# SolderDispenser_v1_1.net
KiCad netlist of a schematic drawn in EAGLE
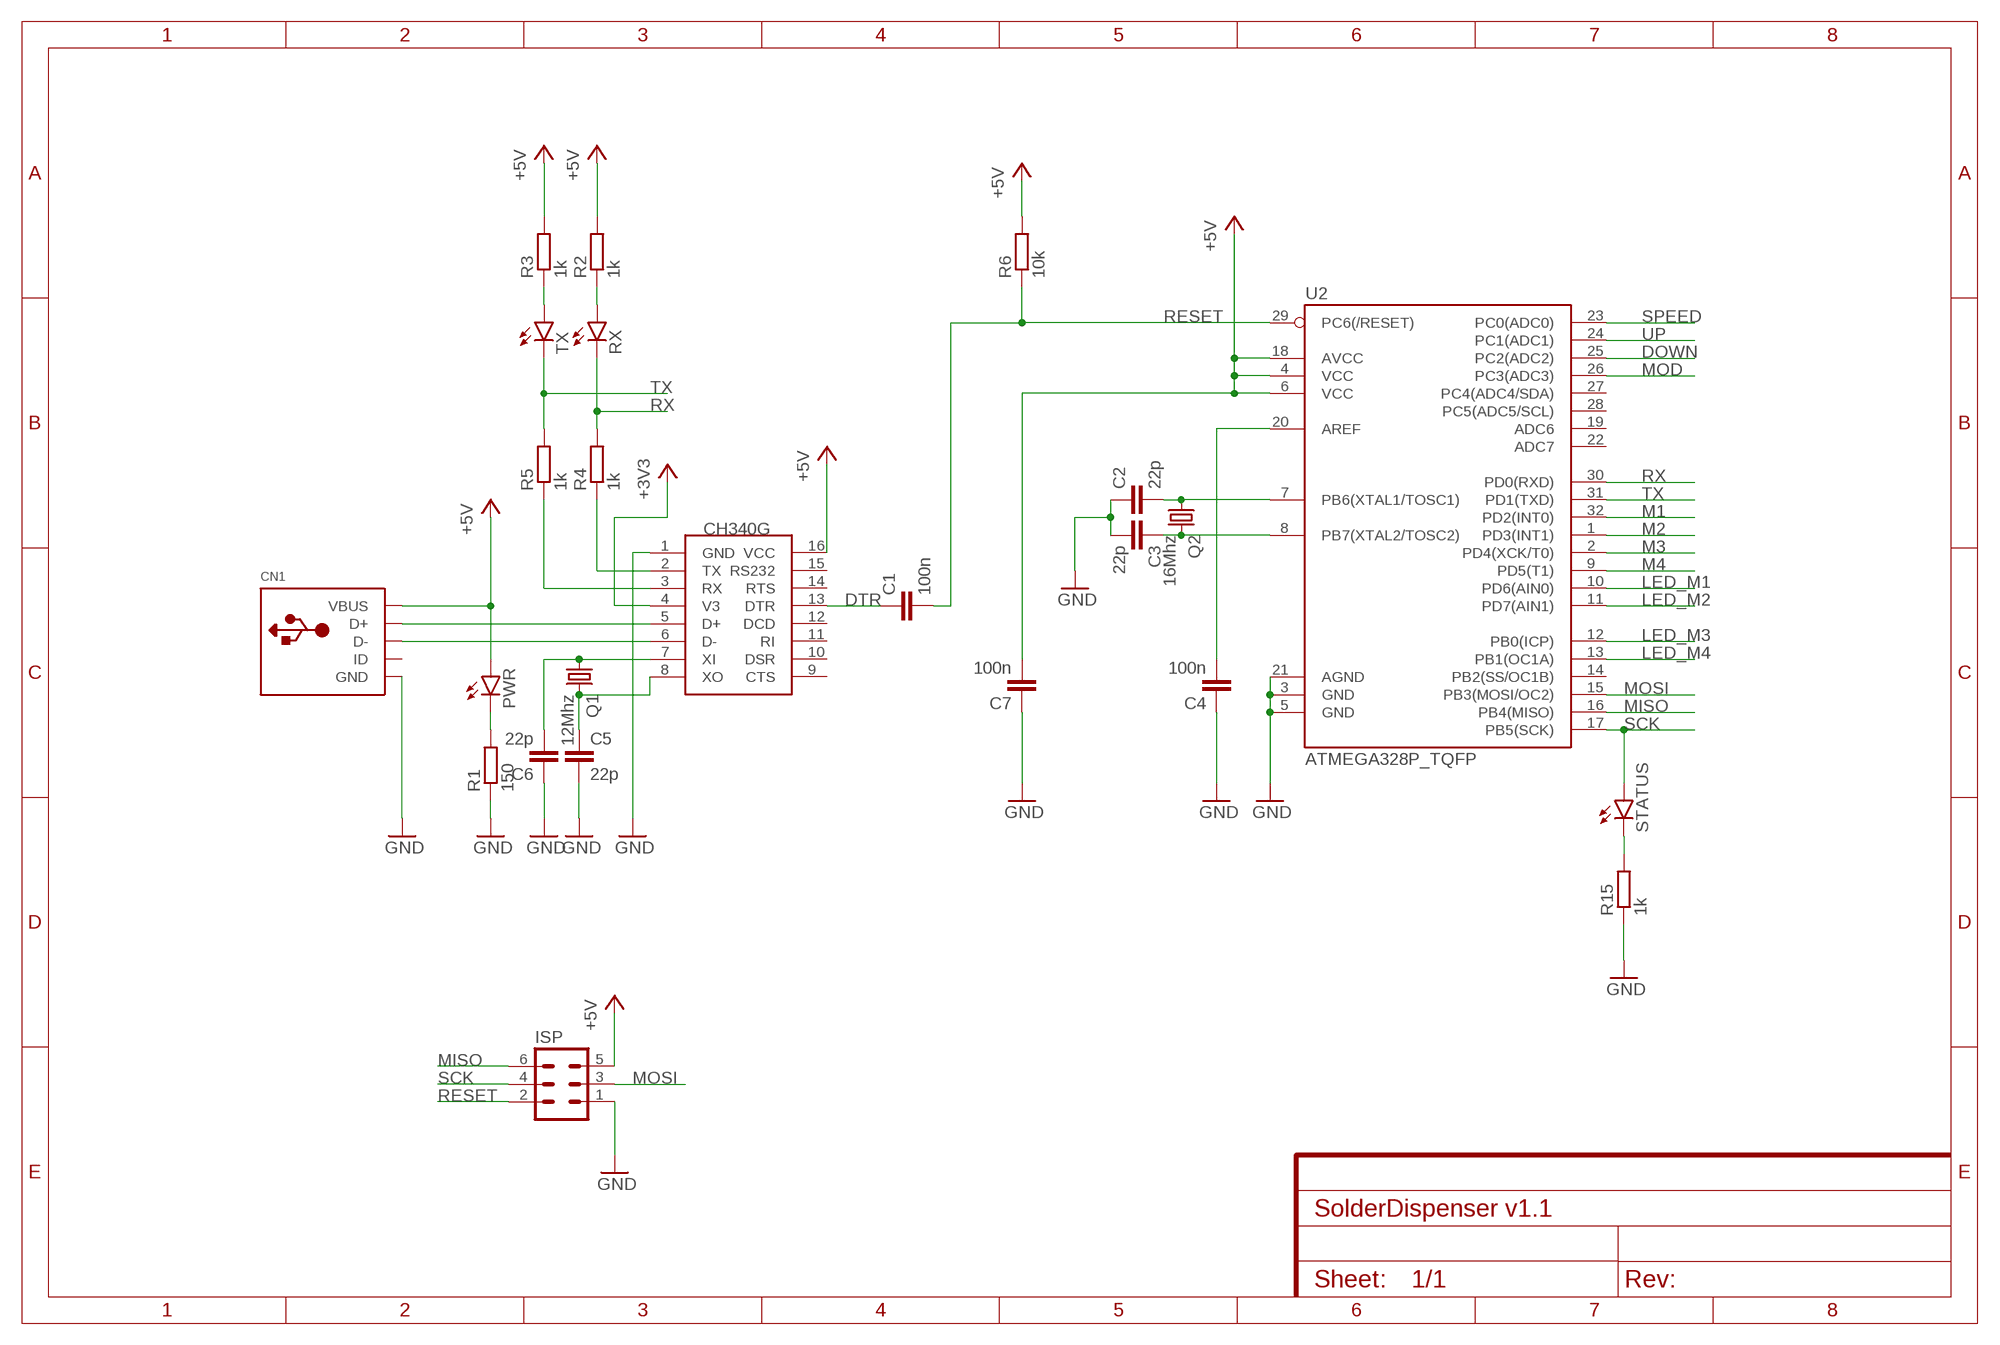
[diagram p0: schematic, sheet 1, part 1 of 2]
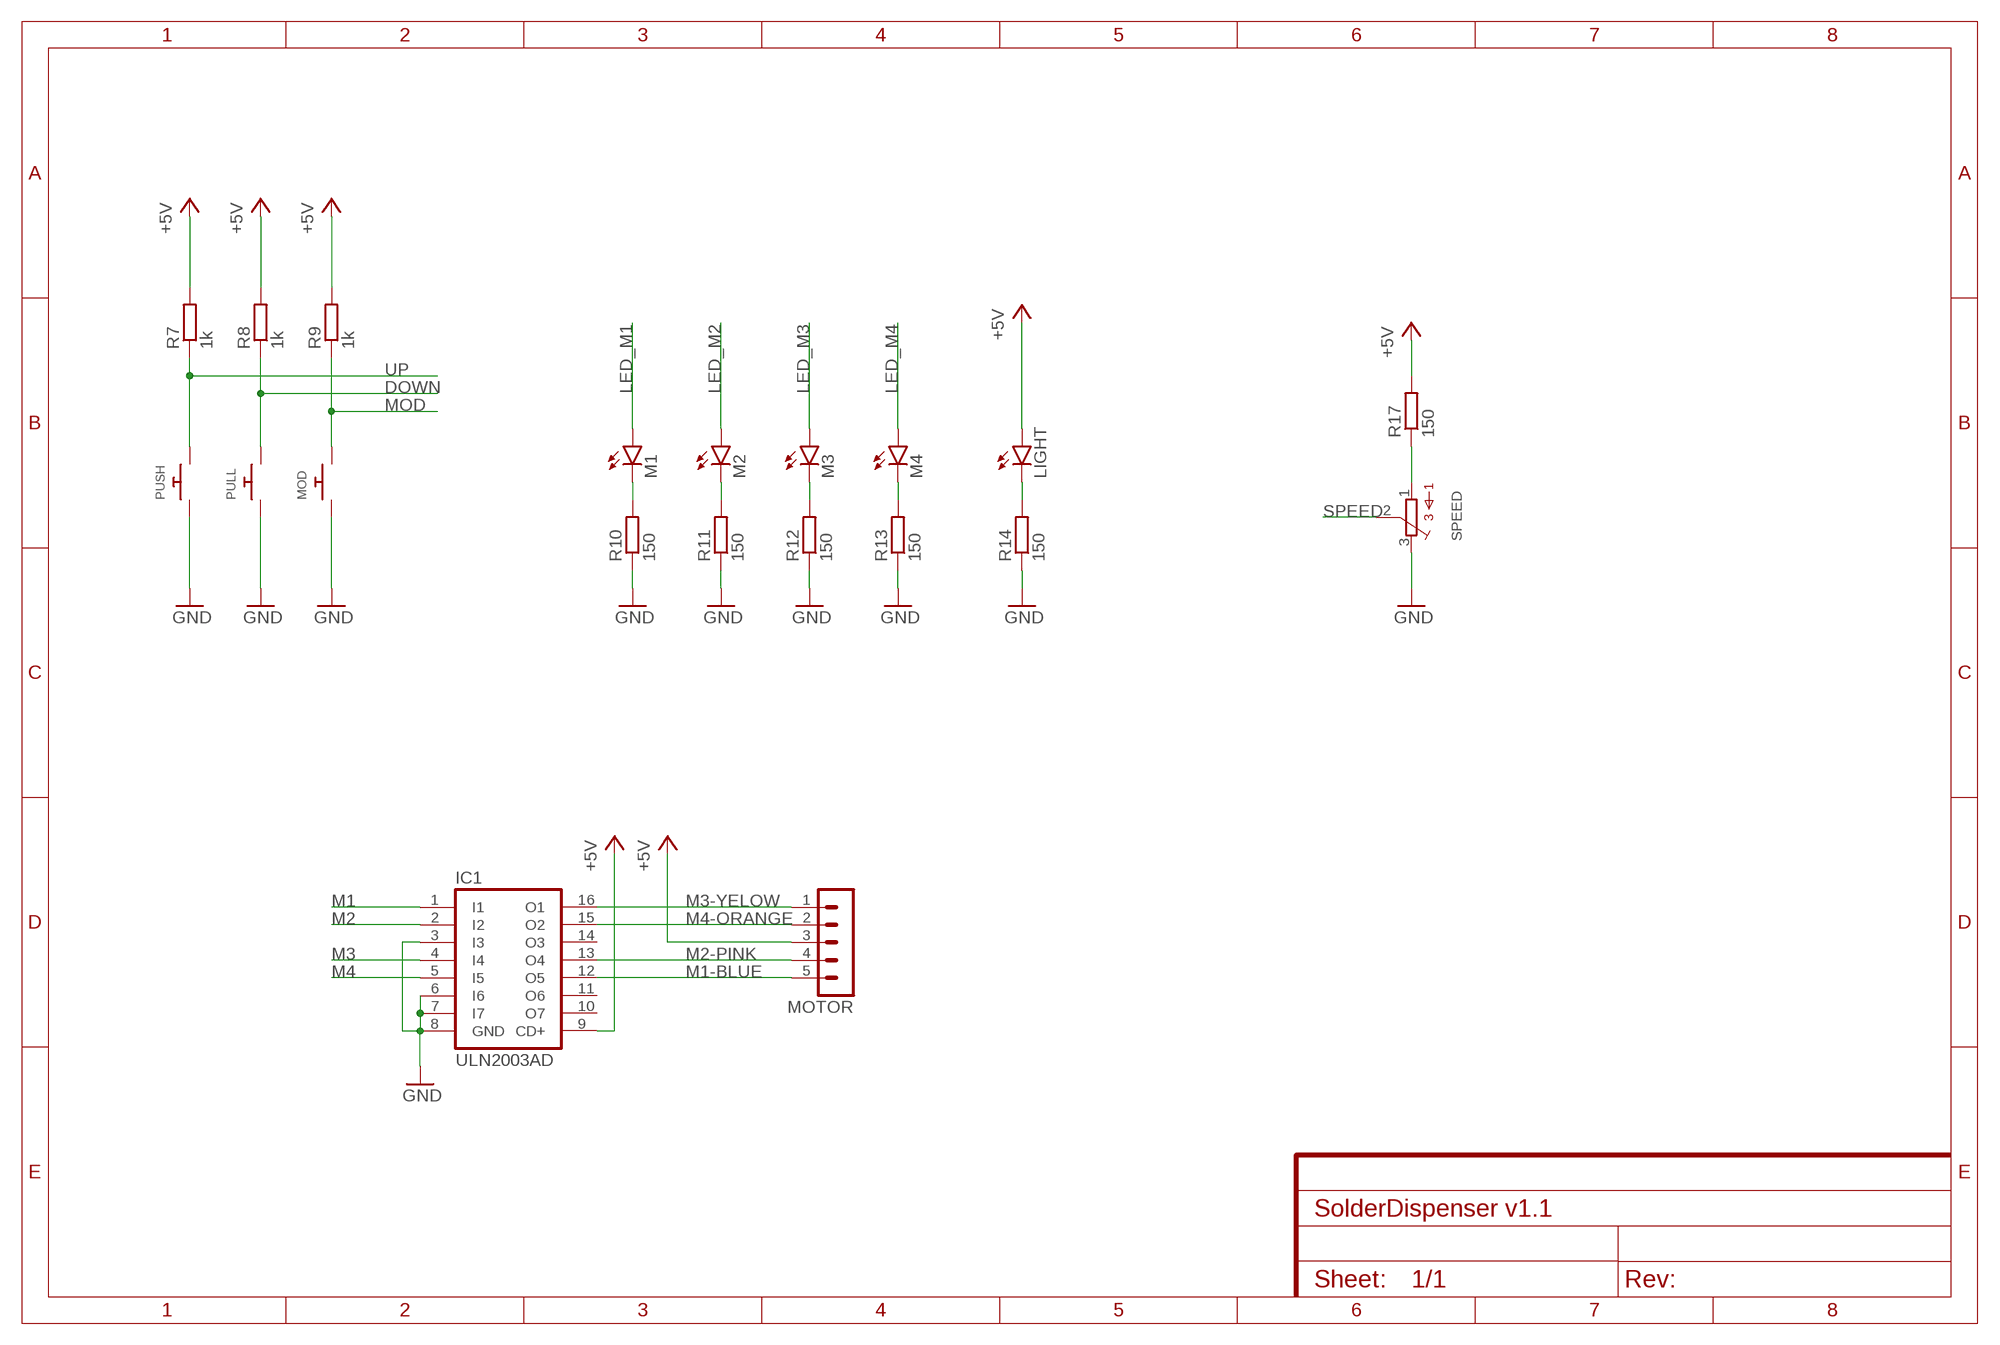
[diagram p1: schematic, sheet 1, part 2 of 2]

(export (version "E")
  (design (tool "Eeschema 10.0.6"))
  (components
    (comp (ref "C1")
      (value "100n")
      (footprint "eagle-import:C0805")
      (libsource (lib "eagle-import") (part "C-EUC0805"))
    )
    (comp (ref "C2")
      (value "22p")
      (footprint "eagle-import:C0805")
      (libsource (lib "eagle-import") (part "C-EUC0805"))
    )
    (comp (ref "C3")
      (value "22p")
      (footprint "eagle-import:C0805")
      (libsource (lib "eagle-import") (part "C-EUC0805"))
    )
    (comp (ref "C4")
      (value "100n")
      (footprint "eagle-import:C0805")
      (libsource (lib "eagle-import") (part "C-EUC0805"))
    )
    (comp (ref "C5")
      (value "22p")
      (footprint "eagle-import:C0805")
      (libsource (lib "eagle-import") (part "C-EUC0805"))
    )
    (comp (ref "C6")
      (value "22p")
      (footprint "eagle-import:C0805")
      (libsource (lib "eagle-import") (part "C-EUC0805"))
    )
    (comp (ref "C7")
      (value "100n")
      (footprint "eagle-import:C0805")
      (libsource (lib "eagle-import") (part "C-EUC0805"))
    )
    (comp (ref "CN1")
      (value "USBMOLEX")
      (footprint "eagle-import:USB-MINIB-THM-MOLEX")
      (libsource (lib "eagle-import") (part "USBMOLEX"))
    )
    (comp (ref "IC1")
      (value "ULN2003AD")
      (footprint "eagle-import:SO16")
      (libsource (lib "eagle-import") (part "ULN2003AD"))
    )
    (comp (ref "ISP")
      (value "MA03-2")
      (footprint "eagle-import:MA03-2")
      (libsource (lib "eagle-import") (part "MA03-2"))
    )
    (comp (ref "LIGHT")
      (value "LED5MM")
      (footprint "eagle-import:LED5MM")
      (libsource (lib "eagle-import") (part "LED5MM"))
    )
    (comp (ref "M1")
      (value "LEDSML0805")
      (footprint "eagle-import:SML0805")
      (libsource (lib "eagle-import") (part "LEDSML0805"))
    )
    (comp (ref "M2")
      (value "LEDSML0805")
      (footprint "eagle-import:SML0805")
      (libsource (lib "eagle-import") (part "LEDSML0805"))
    )
    (comp (ref "M3")
      (value "LEDSML0805")
      (footprint "eagle-import:SML0805")
      (libsource (lib "eagle-import") (part "LEDSML0805"))
    )
    (comp (ref "M4")
      (value "LEDSML0805")
      (footprint "eagle-import:SML0805")
      (libsource (lib "eagle-import") (part "LEDSML0805"))
    )
    (comp (ref "MOD")
      (value "SWITCH_PUSHBUTTONEVQ-PE")
      (footprint "eagle-import:TACT_PANA-EVQ")
      (libsource (lib "eagle-import") (part "SWITCH_PUSHBUTTONEVQ-PE"))
    )
    (comp (ref "MOTOR")
      (value "MA05-1")
      (footprint "eagle-import:MA05-1")
      (libsource (lib "eagle-import") (part "MA05-1"))
    )
    (comp (ref "PULL")
      (value "SWITCH_PUSHBUTTONEVQ-PE")
      (footprint "eagle-import:TACT_PANA-EVQ")
      (libsource (lib "eagle-import") (part "SWITCH_PUSHBUTTONEVQ-PE"))
    )
    (comp (ref "PUSH")
      (value "SWITCH_PUSHBUTTONEVQ-PE")
      (footprint "eagle-import:TACT_PANA-EVQ")
      (libsource (lib "eagle-import") (part "SWITCH_PUSHBUTTONEVQ-PE"))
    )
    (comp (ref "PWR")
      (value "LEDSML0805")
      (footprint "eagle-import:SML0805")
      (libsource (lib "eagle-import") (part "LEDSML0805"))
    )
    (comp (ref "Q1")
      (value "12Mhz")
      (footprint "eagle-import:HC49UP")
      (libsource (lib "eagle-import") (part "CRYSTALHC49UP"))
    )
    (comp (ref "Q2")
      (value "16Mhz")
      (footprint "eagle-import:HC49UP")
      (libsource (lib "eagle-import") (part "CRYSTALHC49UP"))
    )
    (comp (ref "R1")
      (value "150")
      (footprint "eagle-import:R0805")
      (libsource (lib "eagle-import") (part "R-EU_R0805"))
    )
    (comp (ref "R2")
      (value "1k")
      (footprint "eagle-import:R0805")
      (libsource (lib "eagle-import") (part "R-EU_R0805"))
    )
    (comp (ref "R3")
      (value "1k")
      (footprint "eagle-import:R0805")
      (libsource (lib "eagle-import") (part "R-EU_R0805"))
    )
    (comp (ref "R4")
      (value "1k")
      (footprint "eagle-import:R0805")
      (libsource (lib "eagle-import") (part "R-EU_R0805"))
    )
    (comp (ref "R5")
      (value "1k")
      (footprint "eagle-import:R0805")
      (libsource (lib "eagle-import") (part "R-EU_R0805"))
    )
    (comp (ref "R6")
      (value "10k")
      (footprint "eagle-import:R0805")
      (libsource (lib "eagle-import") (part "R-EU_R0805"))
    )
    (comp (ref "R7")
      (value "1k")
      (footprint "eagle-import:R0805")
      (libsource (lib "eagle-import") (part "R-EU_R0805"))
    )
    (comp (ref "R8")
      (value "1k")
      (footprint "eagle-import:R0805")
      (libsource (lib "eagle-import") (part "R-EU_R0805"))
    )
    (comp (ref "R9")
      (value "1k")
      (footprint "eagle-import:R0805")
      (libsource (lib "eagle-import") (part "R-EU_R0805"))
    )
    (comp (ref "R10")
      (value "150")
      (footprint "eagle-import:R0805")
      (libsource (lib "eagle-import") (part "R-EU_R0805"))
    )
    (comp (ref "R11")
      (value "150")
      (footprint "eagle-import:R0805")
      (libsource (lib "eagle-import") (part "R-EU_R0805"))
    )
    (comp (ref "R12")
      (value "150")
      (footprint "eagle-import:R0805")
      (libsource (lib "eagle-import") (part "R-EU_R0805"))
    )
    (comp (ref "R13")
      (value "150")
      (footprint "eagle-import:R0805")
      (libsource (lib "eagle-import") (part "R-EU_R0805"))
    )
    (comp (ref "R14")
      (value "150")
      (footprint "eagle-import:R0805")
      (libsource (lib "eagle-import") (part "R-EU_R0805"))
    )
    (comp (ref "R15")
      (value "1k")
      (footprint "eagle-import:R0805")
      (libsource (lib "eagle-import") (part "R-EU_R0805"))
    )
    (comp (ref "R17")
      (value "150")
      (footprint "eagle-import:R0805")
      (libsource (lib "eagle-import") (part "R-EU_R0805"))
    )
    (comp (ref "RX")
      (value "LEDSML0805")
      (footprint "eagle-import:SML0805")
      (libsource (lib "eagle-import") (part "LEDSML0805"))
    )
    (comp (ref "SPEED")
      (value "3362P")
      (footprint "eagle-import:3362P")
      (libsource (lib "eagle-import") (part "3362P"))
    )
    (comp (ref "STATUS")
      (value "LEDSML0805")
      (footprint "eagle-import:SML0805")
      (libsource (lib "eagle-import") (part "LEDSML0805"))
    )
    (comp (ref "TX")
      (value "LEDSML0805")
      (footprint "eagle-import:SML0805")
      (libsource (lib "eagle-import") (part "LEDSML0805"))
    )
    (comp (ref "U$1")
      (value "CH340G")
      (footprint "eagle-import:SOIC16")
      (libsource (lib "eagle-import") (part "CH340G"))
    )
    (comp (ref "U2")
      (value "ATMEGA328P_TQFP")
      (footprint "eagle-import:TQFP32-08")
      (libsource (lib "eagle-import") (part "ATMEGA328P_TQFP"))
    )
  )
  (nets
    (net (code "1") (name "+3V3") (class "Default")
      (node (ref "U$1") (pin "4") (pinfunction "V3_4") (pintype "bidirectional"))
    )
    (net (code "2") (name "+5V") (class "Default")
      (node (ref "C7") (pin "2") (pinfunction "2_2") (pintype "passive"))
      (node (ref "CN1") (pin "VBUS") (pinfunction "VBUS_VBUS") (pintype "power_in"))
      (node (ref "IC1") (pin "9") (pinfunction "CD+_9") (pintype "passive"))
      (node (ref "ISP") (pin "5") (pinfunction "5_5") (pintype "passive"))
      (node (ref "LIGHT") (pin "A") (pinfunction "A_A") (pintype "passive"))
      (node (ref "MOTOR") (pin "3") (pinfunction "3_3") (pintype "passive"))
      (node (ref "PWR") (pin "A") (pinfunction "A_A") (pintype "passive"))
      (node (ref "R17") (pin "2") (pinfunction "2_2") (pintype "passive"))
      (node (ref "R2") (pin "2") (pinfunction "2_2") (pintype "passive"))
      (node (ref "R3") (pin "2") (pinfunction "2_2") (pintype "passive"))
      (node (ref "R6") (pin "2") (pinfunction "2_2") (pintype "passive"))
      (node (ref "R7") (pin "2") (pinfunction "2_2") (pintype "passive"))
      (node (ref "R8") (pin "2") (pinfunction "2_2") (pintype "passive"))
      (node (ref "R9") (pin "2") (pinfunction "2_2") (pintype "passive"))
      (node (ref "U$1") (pin "16") (pinfunction "VCC_16") (pintype "bidirectional"))
      (node (ref "U2") (pin "18") (pinfunction "AVCC_18") (pintype "bidirectional"))
      (node (ref "U2") (pin "4") (pinfunction "VCC_4") (pintype "bidirectional"))
      (node (ref "U2") (pin "6") (pinfunction "VCC_6") (pintype "bidirectional"))
    )
    (net (code "3") (name "/DOWN") (class "Default")
      (node (ref "PULL") (pin "P$2") (pinfunction "P$2_P$2") (pintype "passive"))
      (node (ref "R8") (pin "1") (pinfunction "1_1") (pintype "passive"))
      (node (ref "U2") (pin "25") (pinfunction "PC2(ADC2)_25") (pintype "bidirectional"))
    )
    (net (code "4") (name "/DTR") (class "Default")
      (node (ref "C1") (pin "1") (pinfunction "1_1") (pintype "passive"))
      (node (ref "U$1") (pin "13") (pinfunction "DTR_13") (pintype "bidirectional"))
    )
    (net (code "5") (name "/LED_M1") (class "Default")
      (node (ref "M1") (pin "A") (pinfunction "A_A") (pintype "passive"))
      (node (ref "U2") (pin "10") (pinfunction "PD6(AIN0)_10") (pintype "bidirectional"))
    )
    (net (code "6") (name "/LED_M2") (class "Default")
      (node (ref "M2") (pin "A") (pinfunction "A_A") (pintype "passive"))
      (node (ref "U2") (pin "11") (pinfunction "PD7(AIN1)_11") (pintype "bidirectional"))
    )
    (net (code "7") (name "/LED_M3") (class "Default")
      (node (ref "M3") (pin "A") (pinfunction "A_A") (pintype "passive"))
      (node (ref "U2") (pin "12") (pinfunction "PB0(ICP)_12") (pintype "bidirectional"))
    )
    (net (code "8") (name "/LED_M4") (class "Default")
      (node (ref "M4") (pin "A") (pinfunction "A_A") (pintype "passive"))
      (node (ref "U2") (pin "13") (pinfunction "PB1(OC1A)_13") (pintype "bidirectional"))
    )
    (net (code "9") (name "/M1") (class "Default")
      (node (ref "IC1") (pin "1") (pinfunction "I1_1") (pintype "input"))
      (node (ref "U2") (pin "32") (pinfunction "PD2(INT0)_32") (pintype "bidirectional"))
    )
    (net (code "10") (name "/M1-BLUE") (class "Default")
      (node (ref "IC1") (pin "12") (pinfunction "O5_12") (pintype "open_collector"))
      (node (ref "MOTOR") (pin "5") (pinfunction "5_5") (pintype "passive"))
    )
    (net (code "11") (name "/M2") (class "Default")
      (node (ref "IC1") (pin "2") (pinfunction "I2_2") (pintype "input"))
      (node (ref "U2") (pin "1") (pinfunction "PD3(INT1)_1") (pintype "bidirectional"))
    )
    (net (code "12") (name "/M2-PINK") (class "Default")
      (node (ref "IC1") (pin "13") (pinfunction "O4_13") (pintype "open_collector"))
      (node (ref "MOTOR") (pin "4") (pinfunction "4_4") (pintype "passive"))
    )
    (net (code "13") (name "/M3") (class "Default")
      (node (ref "IC1") (pin "4") (pinfunction "I4_4") (pintype "input"))
      (node (ref "U2") (pin "2") (pinfunction "PD4(XCK/T0)_2") (pintype "bidirectional"))
    )
    (net (code "14") (name "/M3-YELOW") (class "Default")
      (node (ref "IC1") (pin "16") (pinfunction "O1_16") (pintype "open_collector"))
      (node (ref "MOTOR") (pin "1") (pinfunction "1_1") (pintype "passive"))
    )
    (net (code "15") (name "/M4") (class "Default")
      (node (ref "IC1") (pin "5") (pinfunction "I5_5") (pintype "input"))
      (node (ref "U2") (pin "9") (pinfunction "PD5(T1)_9") (pintype "bidirectional"))
    )
    (net (code "16") (name "/M4-ORANGE") (class "Default")
      (node (ref "IC1") (pin "15") (pinfunction "O2_15") (pintype "open_collector"))
      (node (ref "MOTOR") (pin "2") (pinfunction "2_2") (pintype "passive"))
    )
    (net (code "17") (name "/MISO") (class "Default")
      (node (ref "ISP") (pin "6") (pinfunction "6_6") (pintype "passive"))
      (node (ref "U2") (pin "16") (pinfunction "PB4(MISO)_16") (pintype "bidirectional"))
    )
    (net (code "18") (name "/MOD") (class "Default")
      (node (ref "MOD") (pin "P$2") (pinfunction "P$2_P$2") (pintype "passive"))
      (node (ref "R9") (pin "1") (pinfunction "1_1") (pintype "passive"))
      (node (ref "U2") (pin "26") (pinfunction "PC3(ADC3)_26") (pintype "bidirectional"))
    )
    (net (code "19") (name "/MOSI") (class "Default")
      (node (ref "ISP") (pin "3") (pinfunction "3_3") (pintype "passive"))
      (node (ref "U2") (pin "15") (pinfunction "PB3(MOSI/OC2)_15") (pintype "bidirectional"))
    )
    (net (code "20") (name "/RESET") (class "Default")
      (node (ref "C1") (pin "2") (pinfunction "2_2") (pintype "passive"))
      (node (ref "ISP") (pin "2") (pinfunction "2_2") (pintype "passive"))
      (node (ref "R6") (pin "1") (pinfunction "1_1") (pintype "passive"))
      (node (ref "U2") (pin "29") (pinfunction "PC6(/RESET)_29") (pintype "bidirectional"))
    )
    (net (code "21") (name "/RX") (class "Default")
      (node (ref "R4") (pin "2") (pinfunction "2_2") (pintype "passive"))
      (node (ref "RX") (pin "C") (pinfunction "C_C") (pintype "passive"))
      (node (ref "U2") (pin "30") (pinfunction "PD0(RXD)_30") (pintype "bidirectional"))
    )
    (net (code "22") (name "/SCK") (class "Default")
      (node (ref "ISP") (pin "4") (pinfunction "4_4") (pintype "passive"))
      (node (ref "STATUS") (pin "A") (pinfunction "A_A") (pintype "passive"))
      (node (ref "U2") (pin "17") (pinfunction "PB5(SCK)_17") (pintype "bidirectional"))
    )
    (net (code "23") (name "/SPEED") (class "Default")
      (node (ref "SPEED") (pin "2") (pinfunction "2_2") (pintype "passive"))
      (node (ref "U2") (pin "23") (pinfunction "PC0(ADC0)_23") (pintype "bidirectional"))
    )
    (net (code "24") (name "/TX") (class "Default")
      (node (ref "R5") (pin "2") (pinfunction "2_2") (pintype "passive"))
      (node (ref "TX") (pin "C") (pinfunction "C_C") (pintype "passive"))
      (node (ref "U2") (pin "31") (pinfunction "PD1(TXD)_31") (pintype "bidirectional"))
    )
    (net (code "25") (name "/UP") (class "Default")
      (node (ref "PUSH") (pin "P$2") (pinfunction "P$2_P$2") (pintype "passive"))
      (node (ref "R7") (pin "1") (pinfunction "1_1") (pintype "passive"))
      (node (ref "U2") (pin "24") (pinfunction "PC1(ADC1)_24") (pintype "bidirectional"))
    )
    (net (code "26") (name "GND") (class "Default")
      (node (ref "C2") (pin "1") (pinfunction "1_1") (pintype "passive"))
      (node (ref "C3") (pin "2") (pinfunction "2_2") (pintype "passive"))
      (node (ref "C4") (pin "1") (pinfunction "1_1") (pintype "passive"))
      (node (ref "C5") (pin "2") (pinfunction "2_2") (pintype "passive"))
      (node (ref "C6") (pin "1") (pinfunction "1_1") (pintype "passive"))
      (node (ref "C7") (pin "1") (pinfunction "1_1") (pintype "passive"))
      (node (ref "CN1") (pin "GND") (pinfunction "GND_GND") (pintype "power_in"))
      (node (ref "IC1") (pin "3") (pinfunction "I3_3") (pintype "input"))
      (node (ref "IC1") (pin "6") (pinfunction "I6_6") (pintype "input"))
      (node (ref "IC1") (pin "7") (pinfunction "I7_7") (pintype "input"))
      (node (ref "IC1") (pin "8") (pinfunction "GND_8") (pintype "power_in"))
      (node (ref "ISP") (pin "1") (pinfunction "1_1") (pintype "passive"))
      (node (ref "MOD") (pin "P$1") (pinfunction "P$1_P$1") (pintype "passive"))
      (node (ref "PULL") (pin "P$1") (pinfunction "P$1_P$1") (pintype "passive"))
      (node (ref "PUSH") (pin "P$1") (pinfunction "P$1_P$1") (pintype "passive"))
      (node (ref "R1") (pin "1") (pinfunction "1_1") (pintype "passive"))
      (node (ref "R10") (pin "1") (pinfunction "1_1") (pintype "passive"))
      (node (ref "R11") (pin "1") (pinfunction "1_1") (pintype "passive"))
      (node (ref "R12") (pin "1") (pinfunction "1_1") (pintype "passive"))
      (node (ref "R13") (pin "1") (pinfunction "1_1") (pintype "passive"))
      (node (ref "R14") (pin "1") (pinfunction "1_1") (pintype "passive"))
      (node (ref "R15") (pin "1") (pinfunction "1_1") (pintype "passive"))
      (node (ref "SPEED") (pin "3") (pinfunction "3_3") (pintype "passive"))
      (node (ref "U$1") (pin "1") (pinfunction "GND_1") (pintype "bidirectional"))
      (node (ref "U2") (pin "21") (pinfunction "AGND_21") (pintype "bidirectional"))
      (node (ref "U2") (pin "3") (pinfunction "GND_3") (pintype "bidirectional"))
      (node (ref "U2") (pin "5") (pinfunction "GND_5") (pintype "bidirectional"))
    )
    (net (code "27") (name "Net-(LIGHT-C)") (class "Default")
      (node (ref "LIGHT") (pin "K") (pinfunction "C_K") (pintype "passive"))
      (node (ref "R14") (pin "2") (pinfunction "2_2") (pintype "passive"))
    )
    (net (code "28") (name "Net-(M1-PadC)") (class "Default")
      (node (ref "M1") (pin "C") (pinfunction "C_C") (pintype "passive"))
      (node (ref "R10") (pin "2") (pinfunction "2_2") (pintype "passive"))
    )
    (net (code "29") (name "Net-(M2-PadC)") (class "Default")
      (node (ref "M2") (pin "C") (pinfunction "C_C") (pintype "passive"))
      (node (ref "R11") (pin "2") (pinfunction "2_2") (pintype "passive"))
    )
    (net (code "30") (name "Net-(M3-PadC)") (class "Default")
      (node (ref "M3") (pin "C") (pinfunction "C_C") (pintype "passive"))
      (node (ref "R12") (pin "2") (pinfunction "2_2") (pintype "passive"))
    )
    (net (code "31") (name "Net-(M4-PadC)") (class "Default")
      (node (ref "M4") (pin "C") (pinfunction "C_C") (pintype "passive"))
      (node (ref "R13") (pin "2") (pinfunction "2_2") (pintype "passive"))
    )
    (net (code "32") (name "Net-(PWR-PadC)") (class "Default")
      (node (ref "PWR") (pin "C") (pinfunction "C_C") (pintype "passive"))
      (node (ref "R1") (pin "2") (pinfunction "2_2") (pintype "passive"))
    )
    (net (code "33") (name "Net-(R2-Pad1)") (class "Default")
      (node (ref "R2") (pin "1") (pinfunction "1_1") (pintype "passive"))
      (node (ref "RX") (pin "A") (pinfunction "A_A") (pintype "passive"))
    )
    (net (code "34") (name "Net-(R3-Pad1)") (class "Default")
      (node (ref "R3") (pin "1") (pinfunction "1_1") (pintype "passive"))
      (node (ref "TX") (pin "A") (pinfunction "A_A") (pintype "passive"))
    )
    (net (code "35") (name "Net-(R15-Pad2)") (class "Default")
      (node (ref "R15") (pin "2") (pinfunction "2_2") (pintype "passive"))
      (node (ref "STATUS") (pin "C") (pinfunction "C_C") (pintype "passive"))
    )
    (net (code "36") (name "Net-(R17-Pad1)") (class "Default")
      (node (ref "R17") (pin "1") (pinfunction "1_1") (pintype "passive"))
      (node (ref "SPEED") (pin "1") (pinfunction "1_1") (pintype "passive"))
    )
    (net (code "37") (name "Net-(U$1-D+)") (class "Default")
      (node (ref "CN1") (pin "D+") (pinfunction "D+_D+") (pintype "bidirectional"))
      (node (ref "U$1") (pin "5") (pinfunction "D+_5") (pintype "bidirectional"))
    )
    (net (code "38") (name "Net-(U$1-D-)") (class "Default")
      (node (ref "CN1") (pin "D-") (pinfunction "D-_D-") (pintype "bidirectional"))
      (node (ref "U$1") (pin "6") (pinfunction "D-_6") (pintype "bidirectional"))
    )
    (net (code "39") (name "Net-(U$1-RX)") (class "Default")
      (node (ref "R5") (pin "1") (pinfunction "1_1") (pintype "passive"))
      (node (ref "U$1") (pin "3") (pinfunction "RX_3") (pintype "bidirectional"))
    )
    (net (code "40") (name "Net-(U$1-TX)") (class "Default")
      (node (ref "R4") (pin "1") (pinfunction "1_1") (pintype "passive"))
      (node (ref "U$1") (pin "2") (pinfunction "TX_2") (pintype "bidirectional"))
    )
    (net (code "41") (name "Net-(U$1-XI)") (class "Default")
      (node (ref "C6") (pin "2") (pinfunction "2_2") (pintype "passive"))
      (node (ref "Q1") (pin "1") (pinfunction "1_1") (pintype "passive"))
      (node (ref "U$1") (pin "7") (pinfunction "XI_7") (pintype "bidirectional"))
    )
    (net (code "42") (name "Net-(U$1-XO)") (class "Default")
      (node (ref "C5") (pin "1") (pinfunction "1_1") (pintype "passive"))
      (node (ref "Q1") (pin "2") (pinfunction "2_2") (pintype "passive"))
      (node (ref "U$1") (pin "8") (pinfunction "XO_8") (pintype "bidirectional"))
    )
    (net (code "43") (name "Net-(U2-AREF)") (class "Default")
      (node (ref "C4") (pin "2") (pinfunction "2_2") (pintype "passive"))
      (node (ref "U2") (pin "20") (pinfunction "AREF_20") (pintype "bidirectional"))
    )
    (net (code "44") (name "Net-(U2-PB6(XTAL1{slash}TOSC1))") (class "Default")
      (node (ref "C2") (pin "2") (pinfunction "2_2") (pintype "passive"))
      (node (ref "Q2") (pin "1") (pinfunction "1_1") (pintype "passive"))
      (node (ref "U2") (pin "7") (pinfunction "PB6(XTAL1/TOSC1)_7") (pintype "bidirectional"))
    )
    (net (code "45") (name "Net-(U2-PB7(XTAL2{slash}TOSC2))") (class "Default")
      (node (ref "C3") (pin "1") (pinfunction "1_1") (pintype "passive"))
      (node (ref "Q2") (pin "2") (pinfunction "2_2") (pintype "passive"))
      (node (ref "U2") (pin "8") (pinfunction "PB7(XTAL2/TOSC2)_8") (pintype "bidirectional"))
    )
    (net (code "46") (name "unconnected-(CN1-PadID)") (class "Default")
      (node (ref "CN1") (pin "ID") (pinfunction "ID_ID") (pintype "bidirectional"))
    )
    (net (code "47") (name "unconnected-(IC1-O3-Pad14)") (class "Default")
      (node (ref "IC1") (pin "14") (pinfunction "O3_14") (pintype "open_collector"))
    )
    (net (code "48") (name "unconnected-(IC1-O6-Pad11)") (class "Default")
      (node (ref "IC1") (pin "11") (pinfunction "O6_11") (pintype "open_collector"))
    )
    (net (code "49") (name "unconnected-(IC1-O7-Pad10)") (class "Default")
      (node (ref "IC1") (pin "10") (pinfunction "O7_10") (pintype "open_collector"))
    )
    (net (code "50") (name "unconnected-(U$1-CTS-Pad9)") (class "Default")
      (node (ref "U$1") (pin "9") (pinfunction "CTS_9") (pintype "bidirectional"))
    )
    (net (code "51") (name "unconnected-(U$1-DCD-Pad12)") (class "Default")
      (node (ref "U$1") (pin "12") (pinfunction "DCD_12") (pintype "bidirectional"))
    )
    (net (code "52") (name "unconnected-(U$1-DSR-Pad10)") (class "Default")
      (node (ref "U$1") (pin "10") (pinfunction "DSR_10") (pintype "bidirectional"))
    )
    (net (code "53") (name "unconnected-(U$1-RI-Pad11)") (class "Default")
      (node (ref "U$1") (pin "11") (pinfunction "RI_11") (pintype "bidirectional"))
    )
    (net (code "54") (name "unconnected-(U$1-RS232-Pad15)") (class "Default")
      (node (ref "U$1") (pin "15") (pinfunction "RS232_15") (pintype "bidirectional"))
    )
    (net (code "55") (name "unconnected-(U$1-RTS-Pad14)") (class "Default")
      (node (ref "U$1") (pin "14") (pinfunction "RTS_14") (pintype "bidirectional"))
    )
    (net (code "56") (name "unconnected-(U2-ADC6-Pad19)") (class "Default")
      (node (ref "U2") (pin "19") (pinfunction "ADC6_19") (pintype "bidirectional"))
    )
    (net (code "57") (name "unconnected-(U2-ADC7-Pad22)") (class "Default")
      (node (ref "U2") (pin "22") (pinfunction "ADC7_22") (pintype "bidirectional"))
    )
    (net (code "58") (name "unconnected-(U2-PB2(SS{slash}OC1B)-Pad14)") (class "Default")
      (node (ref "U2") (pin "14") (pinfunction "PB2(SS/OC1B)_14") (pintype "bidirectional"))
    )
    (net (code "59") (name "unconnected-(U2-PC4(ADC4{slash}SDA)-Pad27)") (class "Default")
      (node (ref "U2") (pin "27") (pinfunction "PC4(ADC4/SDA)_27") (pintype "bidirectional"))
    )
    (net (code "60") (name "unconnected-(U2-PC5(ADC5{slash}SCL)-Pad28)") (class "Default")
      (node (ref "U2") (pin "28") (pinfunction "PC5(ADC5/SCL)_28") (pintype "bidirectional"))
    )
  )
)
